# RPL_MCU_E.net
KiCad netlist of a schematic drawn in Altium Designer
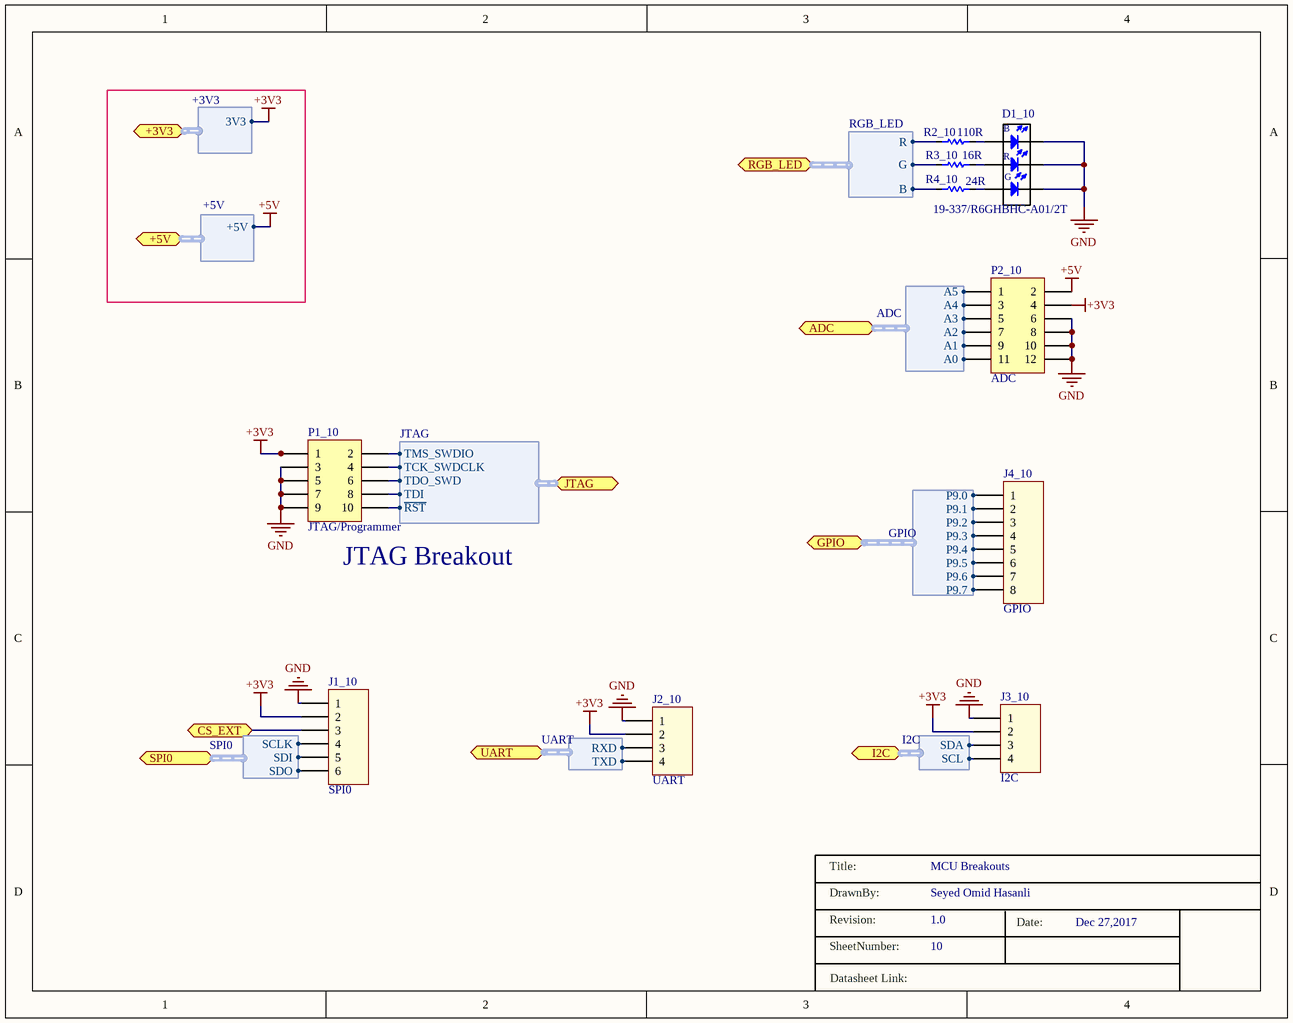
[diagram p0: RPL_MCU_E.SchDoc]

(export (version "E")
  (design (tool "Eeschema 10.0.6"))
  (components
    (comp (ref "D1_10")
      (value "19-337/R6GHBHC-A01/2T")
      (footprint "LED_19-337/R6GHBHC-A01/2T")
      (description "LED Tri-Color Blue/Green/Red 468nm/518nm/632nm 6-Pin T/R")
      (fields (field (name "MF") "Everlight"))
      (libsource (lib "Generic_Library") (part "LED 19-337/R6GHBHC-A01/2T"))
    )
    (comp (ref "J1_10")
      (value "SPI0")
      (footprint "665306124022")
      (description "WR-WTB 1.00 mm SMT Male Vertical Shrouded Header, 6p")
      (fields (field (name "PART NUMBER") "665306124022") (field (name "PUBLISHER") "Wurth Elektronik"))
      (libsource (lib "ALTIUM-WTB_1_00_SMT_MALE_VERTICAL_SHROUDED_HEADER_6653XX124022-rev17a") (part "665306124022"))
    )
    (comp (ref "J2_10")
      (value "UART")
      (footprint "665104131822")
      (description "WR-WTB 1.00 mm SMT Male Horizontal Shrouded, 4p")
      (fields (field (name "PART NUMBER") "665104131822") (field (name "PUBLISHER") "Wurth Elektronik"))
      (libsource (lib "ALTIUM-WTB_1_00_SMT_MALE_VERTICAL_SHROUDED_HEADER_6653XX124022-rev17a") (part "665104131822"))
    )
    (comp (ref "J3_10")
      (value "I2C")
      (footprint "665104131822")
      (description "WR-WTB 1.00 mm SMT Male Horizontal Shrouded, 4p")
      (fields (field (name "PART NUMBER") "665104131822") (field (name "PUBLISHER") "Wurth Elektronik"))
      (libsource (lib "ALTIUM-WTB_1_00_SMT_MALE_VERTICAL_SHROUDED_HEADER_6653XX124022-rev17a") (part "665104131822"))
    )
    (comp (ref "J4_10")
      (value "GPIO")
      (footprint "665308124022")
      (description "WR-WTB 1.00 mm SMT Male Vertical Shrouded Header, 8p")
      (fields (field (name "PART NUMBER") "665308124022") (field (name "PUBLISHER") "Wurth Elektronik"))
      (libsource (lib "ALTIUM-WTB_1_00_SMT_MALE_VERTICAL_SHROUDED_HEADER_6653XX124022-rev17a") (part "665308124022"))
    )
    (comp (ref "P1_10")
      (value "JTAG/Programmer")
      (footprint "FTSH-105-01-XXX-D-K")
      (description "Header, 5-Pin, Dual row")
      (fields (field (name "PUBLISHER") "Altium Limited"))
      (libsource (lib "Miscellaneous Connectors") (part "Header 5X2"))
    )
    (comp (ref "P2_10")
      (value "ADC")
      (footprint "HDR2X6")
      (description "Header, 6-Pin, Dual row")
      (fields (field (name "PUBLISHER") "Altium Limited"))
      (libsource (lib "Miscellaneous Connectors") (part "Header 6X2"))
    )
    (comp (ref "R2_10")
      (value "110R")
      (footprint "SMD Resistors:RES 0805")
      (fields (field (name "Comment") "Res"))
      (libsource (lib "Generic_Library") (part "Res"))
    )
    (comp (ref "R3_10")
      (value "16R")
      (footprint "SMD Resistors:RES 0805")
      (fields (field (name "Comment") "Res"))
      (libsource (lib "Generic_Library") (part "Res"))
    )
    (comp (ref "R4_10")
      (value "24R")
      (footprint "SMD Resistors:RES 0805")
      (fields (field (name "Comment") "Res"))
      (libsource (lib "Generic_Library") (part "Res"))
    )
  )
  (nets
    (net (code "8") (name "+3V3") (class "Default")
      (node (ref "J1_10") (pin "2") (pinfunction "2_2") (pintype "passive"))
      (node (ref "J2_10") (pin "2") (pinfunction "2_2") (pintype "passive"))
      (node (ref "J3_10") (pin "2") (pinfunction "2_2") (pintype "passive"))
      (node (ref "P1_10") (pin "1") (pinfunction "1_1") (pintype "passive"))
      (node (ref "P2_10") (pin "4") (pinfunction "4_4") (pintype "passive"))
    )
    (net (code "9") (name "+5V") (class "Default")
      (node (ref "P2_10") (pin "2") (pinfunction "2_2") (pintype "passive"))
    )
    (net (code "10") (name "/A0") (class "Default")
      (node (ref "P2_10") (pin "11") (pinfunction "11_11") (pintype "passive"))
    )
    (net (code "11") (name "/A1") (class "Default")
      (node (ref "P2_10") (pin "9") (pinfunction "9_9") (pintype "passive"))
    )
    (net (code "12") (name "/A2") (class "Default")
      (node (ref "P2_10") (pin "7") (pinfunction "7_7") (pintype "passive"))
    )
    (net (code "13") (name "/A3") (class "Default")
      (node (ref "P2_10") (pin "5") (pinfunction "5_5") (pintype "passive"))
    )
    (net (code "14") (name "/A4") (class "Default")
      (node (ref "P2_10") (pin "3") (pinfunction "3_3") (pintype "passive"))
    )
    (net (code "15") (name "/A5") (class "Default")
      (node (ref "P2_10") (pin "1") (pinfunction "1_1") (pintype "passive"))
    )
    (net (code "16") (name "/B") (class "Default")
      (node (ref "R4_10") (pin "1") (pinfunction "1_1") (pintype "passive"))
    )
    (net (code "17") (name "/CS_EXT") (class "Default")
      (node (ref "J1_10") (pin "3") (pinfunction "3_3") (pintype "passive"))
    )
    (net (code "18") (name "/G") (class "Default")
      (node (ref "R3_10") (pin "1") (pinfunction "1_1") (pintype "passive"))
    )
    (net (code "19") (name "/P9.0") (class "Default")
      (node (ref "J4_10") (pin "1") (pinfunction "1_1") (pintype "passive"))
    )
    (net (code "20") (name "/P9.1") (class "Default")
      (node (ref "J4_10") (pin "2") (pinfunction "2_2") (pintype "passive"))
    )
    (net (code "21") (name "/P9.2") (class "Default")
      (node (ref "J4_10") (pin "3") (pinfunction "3_3") (pintype "passive"))
    )
    (net (code "22") (name "/P9.3") (class "Default")
      (node (ref "J4_10") (pin "4") (pinfunction "4_4") (pintype "passive"))
    )
    (net (code "23") (name "/P9.4") (class "Default")
      (node (ref "J4_10") (pin "5") (pinfunction "5_5") (pintype "passive"))
    )
    (net (code "24") (name "/P9.5") (class "Default")
      (node (ref "J4_10") (pin "6") (pinfunction "6_6") (pintype "passive"))
    )
    (net (code "25") (name "/P9.6") (class "Default")
      (node (ref "J4_10") (pin "7") (pinfunction "7_7") (pintype "passive"))
    )
    (net (code "26") (name "/P9.7") (class "Default")
      (node (ref "J4_10") (pin "8") (pinfunction "8_8") (pintype "passive"))
    )
    (net (code "27") (name "/R") (class "Default")
      (node (ref "R2_10") (pin "1") (pinfunction "1_1") (pintype "passive"))
    )
    (net (code "28") (name "/RXD") (class "Default")
      (node (ref "J2_10") (pin "3") (pinfunction "3_3") (pintype "passive"))
    )
    (net (code "29") (name "/SCL") (class "Default")
      (node (ref "J3_10") (pin "4") (pinfunction "4_4") (pintype "passive"))
    )
    (net (code "30") (name "/SCLK") (class "Default")
      (node (ref "J1_10") (pin "4") (pinfunction "4_4") (pintype "passive"))
    )
    (net (code "31") (name "/SDA") (class "Default")
      (node (ref "J3_10") (pin "3") (pinfunction "3_3") (pintype "passive"))
    )
    (net (code "32") (name "/SDI") (class "Default")
      (node (ref "J1_10") (pin "5") (pinfunction "5_5") (pintype "passive"))
    )
    (net (code "33") (name "/SDO") (class "Default")
      (node (ref "J1_10") (pin "6") (pinfunction "6_6") (pintype "passive"))
    )
    (net (code "34") (name "/TCK_SWDCLK") (class "Default")
      (node (ref "P1_10") (pin "4") (pinfunction "4_4") (pintype "passive"))
    )
    (net (code "35") (name "/TDI") (class "Default")
      (node (ref "P1_10") (pin "8") (pinfunction "8_8") (pintype "passive"))
    )
    (net (code "36") (name "/TDO_SWD") (class "Default")
      (node (ref "P1_10") (pin "6") (pinfunction "6_6") (pintype "passive"))
    )
    (net (code "37") (name "/TMS_SWDIO") (class "Default")
      (node (ref "P1_10") (pin "2") (pinfunction "2_2") (pintype "passive"))
    )
    (net (code "38") (name "/TXD") (class "Default")
      (node (ref "J2_10") (pin "4") (pinfunction "4_4") (pintype "passive"))
    )
    (net (code "48") (name "/~{RST}") (class "Default")
      (node (ref "P1_10") (pin "10") (pinfunction "10_10") (pintype "passive"))
    )
    (net (code "49") (name "GND") (class "Default")
      (node (ref "D1_10") (pin "1") (pinfunction "C1_1") (pintype "passive"))
      (node (ref "D1_10") (pin "2") (pinfunction "C2_2") (pintype "passive"))
      (node (ref "D1_10") (pin "3") (pinfunction "C3_3") (pintype "passive"))
      (node (ref "J1_10") (pin "1") (pinfunction "1_1") (pintype "passive"))
      (node (ref "J2_10") (pin "1") (pinfunction "1_1") (pintype "passive"))
      (node (ref "J3_10") (pin "1") (pinfunction "1_1") (pintype "passive"))
      (node (ref "P1_10") (pin "3") (pinfunction "3_3") (pintype "passive"))
      (node (ref "P1_10") (pin "5") (pinfunction "5_5") (pintype "passive"))
      (node (ref "P1_10") (pin "7") (pinfunction "7_7") (pintype "passive"))
      (node (ref "P1_10") (pin "9") (pinfunction "9_9") (pintype "passive"))
      (node (ref "P2_10") (pin "10") (pinfunction "10_10") (pintype "passive"))
      (node (ref "P2_10") (pin "12") (pinfunction "12_12") (pintype "passive"))
      (node (ref "P2_10") (pin "6") (pinfunction "6_6") (pintype "passive"))
      (node (ref "P2_10") (pin "8") (pinfunction "8_8") (pintype "passive"))
    )
    (net (code "50") (name "Net-(D1_10-A1)") (class "Default")
      (node (ref "D1_10") (pin "4") (pinfunction "A1_4") (pintype "passive"))
      (node (ref "R2_10") (pin "2") (pinfunction "2_2") (pintype "passive"))
    )
    (net (code "51") (name "Net-(D1_10-A2)") (class "Default")
      (node (ref "D1_10") (pin "5") (pinfunction "A2_5") (pintype "passive"))
      (node (ref "R3_10") (pin "2") (pinfunction "2_2") (pintype "passive"))
    )
    (net (code "52") (name "Net-(D1_10-A3)") (class "Default")
      (node (ref "D1_10") (pin "6") (pinfunction "A3_6") (pintype "passive"))
      (node (ref "R4_10") (pin "2") (pinfunction "2_2") (pintype "passive"))
    )
  )
)
